# LM_HTR_001_TEST.net
KiCad netlist of a schematic drawn in Altium Designer
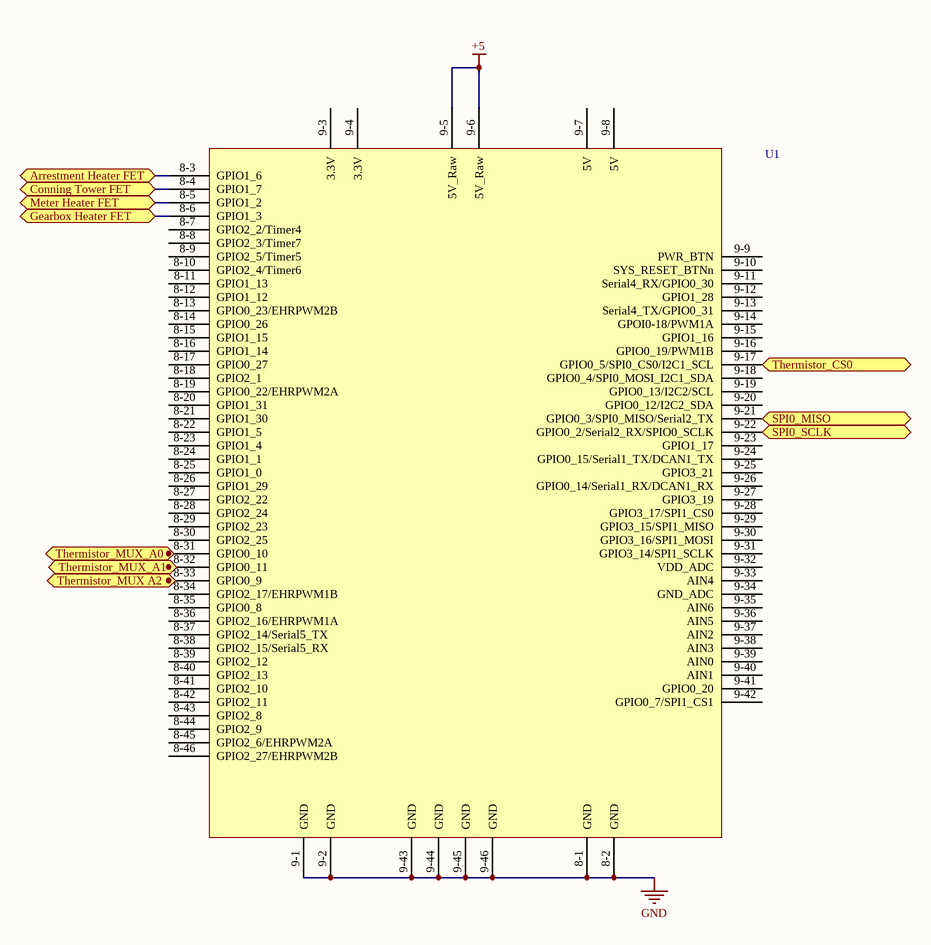
[diagram p0: LM_HTR_001_TEST.SchDoc]

(export (version "E")
  (design (tool "Eeschema 10.0.6"))
  (components
    (comp (ref "U1")
      (value "BBB")
      (footprint "Beaglebone Black")
      (description "Beaglebone Black")
      (libsource (lib "ZLS_Schematic_lib") (part "Beaglebone_Black"))
    )
  )
  (nets
    (net (code "1") (name "+5") (class "Default")
      (node (ref "U1") (pin "9-5") (pinfunction "5V_Raw_9-5") (pintype "passive"))
      (node (ref "U1") (pin "9-6") (pinfunction "5V_Raw_9-6") (pintype "passive"))
    )
    (net (code "2") (name "/Arrestment Heater FET") (class "Default")
      (node (ref "U1") (pin "8-3") (pinfunction "GPIO1_6_8-3") (pintype "passive"))
    )
    (net (code "3") (name "/Conning Tower FET") (class "Default")
      (node (ref "U1") (pin "8-4") (pinfunction "GPIO1_7_8-4") (pintype "passive"))
    )
    (net (code "4") (name "/Gearbox Heater FET") (class "Default")
      (node (ref "U1") (pin "8-6") (pinfunction "GPIO1_3_8-6") (pintype "passive"))
    )
    (net (code "5") (name "/Meter Heater FET") (class "Default")
      (node (ref "U1") (pin "8-5") (pinfunction "GPIO1_2_8-5") (pintype "passive"))
    )
    (net (code "6") (name "/SPI0_MISO") (class "Default")
      (node (ref "U1") (pin "9-21") (pinfunction "GPIO0_3/SPI0_MISO/Serial2_TX_9-21") (pintype "passive"))
    )
    (net (code "7") (name "/SPI0_SCLK") (class "Default")
      (node (ref "U1") (pin "9-22") (pinfunction "GPIO0_2/Serial2_RX/SPIO0_SCLK_9-22") (pintype "passive"))
    )
    (net (code "8") (name "/Thermistor_CS0") (class "Default")
      (node (ref "U1") (pin "9-17") (pinfunction "GPIO0_5/SPI0_CS0/I2C1_SCL_9-17") (pintype "passive"))
    )
    (net (code "12") (name "GND") (class "Default")
      (node (ref "U1") (pin "8-1") (pinfunction "GND_8-1") (pintype "passive"))
      (node (ref "U1") (pin "8-2") (pinfunction "GND_8-2") (pintype "passive"))
      (node (ref "U1") (pin "9-1") (pinfunction "GND_9-1") (pintype "passive"))
      (node (ref "U1") (pin "9-2") (pinfunction "GND_9-2") (pintype "passive"))
      (node (ref "U1") (pin "9-43") (pinfunction "GND_9-43") (pintype "passive"))
      (node (ref "U1") (pin "9-44") (pinfunction "GND_9-44") (pintype "passive"))
      (node (ref "U1") (pin "9-45") (pinfunction "GND_9-45") (pintype "passive"))
      (node (ref "U1") (pin "9-46") (pinfunction "GND_9-46") (pintype "passive"))
    )
    (net (code "13") (name "unconnected-(U1-3.3V-Pad9-3)") (class "Default")
      (node (ref "U1") (pin "9-3") (pinfunction "3.3V_9-3") (pintype "passive"))
    )
    (net (code "14") (name "unconnected-(U1-3.3V-Pad9-4)") (class "Default")
      (node (ref "U1") (pin "9-4") (pinfunction "3.3V_9-4") (pintype "passive"))
    )
    (net (code "15") (name "unconnected-(U1-5V-Pad9-7)") (class "Default")
      (node (ref "U1") (pin "9-7") (pinfunction "5V_9-7") (pintype "passive"))
    )
    (net (code "16") (name "unconnected-(U1-5V-Pad9-8)") (class "Default")
      (node (ref "U1") (pin "9-8") (pinfunction "5V_9-8") (pintype "passive"))
    )
    (net (code "17") (name "unconnected-(U1-AIN0-Pad9-39)") (class "Default")
      (node (ref "U1") (pin "9-39") (pinfunction "AIN0_9-39") (pintype "passive"))
    )
    (net (code "18") (name "unconnected-(U1-AIN1-Pad9-40)") (class "Default")
      (node (ref "U1") (pin "9-40") (pinfunction "AIN1_9-40") (pintype "passive"))
    )
    (net (code "19") (name "unconnected-(U1-AIN2-Pad9-37)") (class "Default")
      (node (ref "U1") (pin "9-37") (pinfunction "AIN2_9-37") (pintype "passive"))
    )
    (net (code "20") (name "unconnected-(U1-AIN3-Pad9-38)") (class "Default")
      (node (ref "U1") (pin "9-38") (pinfunction "AIN3_9-38") (pintype "passive"))
    )
    (net (code "21") (name "unconnected-(U1-AIN4-Pad9-33)") (class "Default")
      (node (ref "U1") (pin "9-33") (pinfunction "AIN4_9-33") (pintype "passive"))
    )
    (net (code "22") (name "unconnected-(U1-AIN5-Pad9-36)") (class "Default")
      (node (ref "U1") (pin "9-36") (pinfunction "AIN5_9-36") (pintype "passive"))
    )
    (net (code "23") (name "unconnected-(U1-AIN6-Pad9-35)") (class "Default")
      (node (ref "U1") (pin "9-35") (pinfunction "AIN6_9-35") (pintype "passive"))
    )
    (net (code "24") (name "unconnected-(U1-GND_ADC-Pad9-34)") (class "Default")
      (node (ref "U1") (pin "9-34") (pinfunction "GND_ADC_9-34") (pintype "passive"))
    )
    (net (code "25") (name "unconnected-(U1-GPIO0_4{slash}SPI0_MOSI_I2C1_SDA-Pad9-18)") (class "Default")
      (node (ref "U1") (pin "9-18") (pinfunction "GPIO0_4/SPI0_MOSI_I2C1_SDA_9-18") (pintype "passive"))
    )
    (net (code "26") (name "unconnected-(U1-GPIO0_7{slash}SPI1_CS1-Pad9-42)") (class "Default")
      (node (ref "U1") (pin "9-42") (pinfunction "GPIO0_7/SPI1_CS1_9-42") (pintype "passive"))
    )
    (net (code "27") (name "unconnected-(U1-GPIO0_8-Pad8-35)") (class "Default")
      (node (ref "U1") (pin "8-35") (pinfunction "GPIO0_8_8-35") (pintype "passive"))
    )
    (net (code "28") (name "unconnected-(U1-GPIO0_9-Pad8-33)") (class "Default")
      (node (ref "U1") (pin "8-33") (pinfunction "GPIO0_9_8-33") (pintype "passive"))
    )
    (net (code "29") (name "unconnected-(U1-GPIO0_10-Pad8-31)") (class "Default")
      (node (ref "U1") (pin "8-31") (pinfunction "GPIO0_10_8-31") (pintype "passive"))
    )
    (net (code "30") (name "unconnected-(U1-GPIO0_11-Pad8-32)") (class "Default")
      (node (ref "U1") (pin "8-32") (pinfunction "GPIO0_11_8-32") (pintype "passive"))
    )
    (net (code "31") (name "unconnected-(U1-GPIO0_12{slash}I2C2_SDA-Pad9-20)") (class "Default")
      (node (ref "U1") (pin "9-20") (pinfunction "GPIO0_12/I2C2_SDA_9-20") (pintype "passive"))
    )
    (net (code "32") (name "unconnected-(U1-GPIO0_13{slash}I2C2{slash}SCL-Pad9-19)") (class "Default")
      (node (ref "U1") (pin "9-19") (pinfunction "GPIO0_13/I2C2/SCL_9-19") (pintype "passive"))
    )
    (net (code "33") (name "unconnected-(U1-GPIO0_14{slash}Serial1_RX{slash}DCAN1_RX-Pad9-26)") (class "Default")
      (node (ref "U1") (pin "9-26") (pinfunction "GPIO0_14/Serial1_RX/DCAN1_RX_9-26") (pintype "passive"))
    )
    (net (code "34") (name "unconnected-(U1-GPIO0_15{slash}Serial1_TX{slash}DCAN1_TX-Pad9-24)") (class "Default")
      (node (ref "U1") (pin "9-24") (pinfunction "GPIO0_15/Serial1_TX/DCAN1_TX_9-24") (pintype "passive"))
    )
    (net (code "35") (name "unconnected-(U1-GPIO0_19{slash}PWM1B-Pad9-16)") (class "Default")
      (node (ref "U1") (pin "9-16") (pinfunction "GPIO0_19/PWM1B_9-16") (pintype "passive"))
    )
    (net (code "36") (name "unconnected-(U1-GPIO0_20-Pad9-41)") (class "Default")
      (node (ref "U1") (pin "9-41") (pinfunction "GPIO0_20_9-41") (pintype "passive"))
    )
    (net (code "37") (name "unconnected-(U1-GPIO0_22{slash}EHRPWM2A-Pad8-19)") (class "Default")
      (node (ref "U1") (pin "8-19") (pinfunction "GPIO0_22/EHRPWM2A_8-19") (pintype "passive"))
    )
    (net (code "38") (name "unconnected-(U1-GPIO0_23{slash}EHRPWM2B-Pad8-13)") (class "Default")
      (node (ref "U1") (pin "8-13") (pinfunction "GPIO0_23/EHRPWM2B_8-13") (pintype "passive"))
    )
    (net (code "39") (name "unconnected-(U1-GPIO0_26-Pad8-14)") (class "Default")
      (node (ref "U1") (pin "8-14") (pinfunction "GPIO0_26_8-14") (pintype "passive"))
    )
    (net (code "40") (name "unconnected-(U1-GPIO0_27-Pad8-17)") (class "Default")
      (node (ref "U1") (pin "8-17") (pinfunction "GPIO0_27_8-17") (pintype "passive"))
    )
    (net (code "41") (name "unconnected-(U1-GPIO1_0-Pad8-25)") (class "Default")
      (node (ref "U1") (pin "8-25") (pinfunction "GPIO1_0_8-25") (pintype "passive"))
    )
    (net (code "42") (name "unconnected-(U1-GPIO1_1-Pad8-24)") (class "Default")
      (node (ref "U1") (pin "8-24") (pinfunction "GPIO1_1_8-24") (pintype "passive"))
    )
    (net (code "43") (name "unconnected-(U1-GPIO1_4-Pad8-23)") (class "Default")
      (node (ref "U1") (pin "8-23") (pinfunction "GPIO1_4_8-23") (pintype "passive"))
    )
    (net (code "44") (name "unconnected-(U1-GPIO1_5-Pad8-22)") (class "Default")
      (node (ref "U1") (pin "8-22") (pinfunction "GPIO1_5_8-22") (pintype "passive"))
    )
    (net (code "45") (name "unconnected-(U1-GPIO1_12-Pad8-12)") (class "Default")
      (node (ref "U1") (pin "8-12") (pinfunction "GPIO1_12_8-12") (pintype "passive"))
    )
    (net (code "46") (name "unconnected-(U1-GPIO1_13-Pad8-11)") (class "Default")
      (node (ref "U1") (pin "8-11") (pinfunction "GPIO1_13_8-11") (pintype "passive"))
    )
    (net (code "47") (name "unconnected-(U1-GPIO1_14-Pad8-16)") (class "Default")
      (node (ref "U1") (pin "8-16") (pinfunction "GPIO1_14_8-16") (pintype "passive"))
    )
    (net (code "48") (name "unconnected-(U1-GPIO1_15-Pad8-15)") (class "Default")
      (node (ref "U1") (pin "8-15") (pinfunction "GPIO1_15_8-15") (pintype "passive"))
    )
    (net (code "49") (name "unconnected-(U1-GPIO1_16-Pad9-15)") (class "Default")
      (node (ref "U1") (pin "9-15") (pinfunction "GPIO1_16_9-15") (pintype "passive"))
    )
    (net (code "50") (name "unconnected-(U1-GPIO1_17-Pad9-23)") (class "Default")
      (node (ref "U1") (pin "9-23") (pinfunction "GPIO1_17_9-23") (pintype "passive"))
    )
    (net (code "51") (name "unconnected-(U1-GPIO1_28-Pad9-12)") (class "Default")
      (node (ref "U1") (pin "9-12") (pinfunction "GPIO1_28_9-12") (pintype "passive"))
    )
    (net (code "52") (name "unconnected-(U1-GPIO1_29-Pad8-26)") (class "Default")
      (node (ref "U1") (pin "8-26") (pinfunction "GPIO1_29_8-26") (pintype "passive"))
    )
    (net (code "53") (name "unconnected-(U1-GPIO1_30-Pad8-21)") (class "Default")
      (node (ref "U1") (pin "8-21") (pinfunction "GPIO1_30_8-21") (pintype "passive"))
    )
    (net (code "54") (name "unconnected-(U1-GPIO1_31-Pad8-20)") (class "Default")
      (node (ref "U1") (pin "8-20") (pinfunction "GPIO1_31_8-20") (pintype "passive"))
    )
    (net (code "55") (name "unconnected-(U1-GPIO2_1-Pad8-18)") (class "Default")
      (node (ref "U1") (pin "8-18") (pinfunction "GPIO2_1_8-18") (pintype "passive"))
    )
    (net (code "56") (name "unconnected-(U1-GPIO2_2{slash}Timer4-Pad8-7)") (class "Default")
      (node (ref "U1") (pin "8-7") (pinfunction "GPIO2_2/Timer4_8-7") (pintype "passive"))
    )
    (net (code "57") (name "unconnected-(U1-GPIO2_3{slash}Timer7-Pad8-8)") (class "Default")
      (node (ref "U1") (pin "8-8") (pinfunction "GPIO2_3/Timer7_8-8") (pintype "passive"))
    )
    (net (code "58") (name "unconnected-(U1-GPIO2_4{slash}Timer6-Pad8-10)") (class "Default")
      (node (ref "U1") (pin "8-10") (pinfunction "GPIO2_4/Timer6_8-10") (pintype "passive"))
    )
    (net (code "59") (name "unconnected-(U1-GPIO2_5{slash}Timer5-Pad8-9)") (class "Default")
      (node (ref "U1") (pin "8-9") (pinfunction "GPIO2_5/Timer5_8-9") (pintype "passive"))
    )
    (net (code "60") (name "unconnected-(U1-GPIO2_6{slash}EHRPWM2A-Pad8-45)") (class "Default")
      (node (ref "U1") (pin "8-45") (pinfunction "GPIO2_6/EHRPWM2A_8-45") (pintype "passive"))
    )
    (net (code "61") (name "unconnected-(U1-GPIO2_8-Pad8-43)") (class "Default")
      (node (ref "U1") (pin "8-43") (pinfunction "GPIO2_8_8-43") (pintype "passive"))
    )
    (net (code "62") (name "unconnected-(U1-GPIO2_9-Pad8-44)") (class "Default")
      (node (ref "U1") (pin "8-44") (pinfunction "GPIO2_9_8-44") (pintype "passive"))
    )
    (net (code "63") (name "unconnected-(U1-GPIO2_10-Pad8-41)") (class "Default")
      (node (ref "U1") (pin "8-41") (pinfunction "GPIO2_10_8-41") (pintype "passive"))
    )
    (net (code "64") (name "unconnected-(U1-GPIO2_11-Pad8-42)") (class "Default")
      (node (ref "U1") (pin "8-42") (pinfunction "GPIO2_11_8-42") (pintype "passive"))
    )
    (net (code "65") (name "unconnected-(U1-GPIO2_12-Pad8-39)") (class "Default")
      (node (ref "U1") (pin "8-39") (pinfunction "GPIO2_12_8-39") (pintype "passive"))
    )
    (net (code "66") (name "unconnected-(U1-GPIO2_13-Pad8-40)") (class "Default")
      (node (ref "U1") (pin "8-40") (pinfunction "GPIO2_13_8-40") (pintype "passive"))
    )
    (net (code "67") (name "unconnected-(U1-GPIO2_14{slash}Serial5_TX-Pad8-37)") (class "Default")
      (node (ref "U1") (pin "8-37") (pinfunction "GPIO2_14/Serial5_TX_8-37") (pintype "passive"))
    )
    (net (code "68") (name "unconnected-(U1-GPIO2_15{slash}Serial5_RX-Pad8-38)") (class "Default")
      (node (ref "U1") (pin "8-38") (pinfunction "GPIO2_15/Serial5_RX_8-38") (pintype "passive"))
    )
    (net (code "69") (name "unconnected-(U1-GPIO2_16{slash}EHRPWM1A-Pad8-36)") (class "Default")
      (node (ref "U1") (pin "8-36") (pinfunction "GPIO2_16/EHRPWM1A_8-36") (pintype "passive"))
    )
    (net (code "70") (name "unconnected-(U1-GPIO2_17{slash}EHRPWM1B-Pad8-34)") (class "Default")
      (node (ref "U1") (pin "8-34") (pinfunction "GPIO2_17/EHRPWM1B_8-34") (pintype "passive"))
    )
    (net (code "71") (name "unconnected-(U1-GPIO2_22-Pad8-27)") (class "Default")
      (node (ref "U1") (pin "8-27") (pinfunction "GPIO2_22_8-27") (pintype "passive"))
    )
    (net (code "72") (name "unconnected-(U1-GPIO2_23-Pad8-29)") (class "Default")
      (node (ref "U1") (pin "8-29") (pinfunction "GPIO2_23_8-29") (pintype "passive"))
    )
    (net (code "73") (name "unconnected-(U1-GPIO2_24-Pad8-28)") (class "Default")
      (node (ref "U1") (pin "8-28") (pinfunction "GPIO2_24_8-28") (pintype "passive"))
    )
    (net (code "74") (name "unconnected-(U1-GPIO2_25-Pad8-30)") (class "Default")
      (node (ref "U1") (pin "8-30") (pinfunction "GPIO2_25_8-30") (pintype "passive"))
    )
    (net (code "75") (name "unconnected-(U1-GPIO2_27{slash}EHRPWM2B-Pad8-46)") (class "Default")
      (node (ref "U1") (pin "8-46") (pinfunction "GPIO2_27/EHRPWM2B_8-46") (pintype "passive"))
    )
    (net (code "76") (name "unconnected-(U1-GPIO3_14{slash}SPI1_SCLK-Pad9-31)") (class "Default")
      (node (ref "U1") (pin "9-31") (pinfunction "GPIO3_14/SPI1_SCLK_9-31") (pintype "passive"))
    )
    (net (code "77") (name "unconnected-(U1-GPIO3_15{slash}SPI1_MISO-Pad9-29)") (class "Default")
      (node (ref "U1") (pin "9-29") (pinfunction "GPIO3_15/SPI1_MISO_9-29") (pintype "passive"))
    )
    (net (code "78") (name "unconnected-(U1-GPIO3_16{slash}SPI1_MOSI-Pad9-30)") (class "Default")
      (node (ref "U1") (pin "9-30") (pinfunction "GPIO3_16/SPI1_MOSI_9-30") (pintype "passive"))
    )
    (net (code "79") (name "unconnected-(U1-GPIO3_17{slash}SPI1_CS0-Pad9-28)") (class "Default")
      (node (ref "U1") (pin "9-28") (pinfunction "GPIO3_17/SPI1_CS0_9-28") (pintype "passive"))
    )
    (net (code "80") (name "unconnected-(U1-GPIO3_19-Pad9-27)") (class "Default")
      (node (ref "U1") (pin "9-27") (pinfunction "GPIO3_19_9-27") (pintype "passive"))
    )
    (net (code "81") (name "unconnected-(U1-GPIO3_21-Pad9-25)") (class "Default")
      (node (ref "U1") (pin "9-25") (pinfunction "GPIO3_21_9-25") (pintype "passive"))
    )
    (net (code "82") (name "unconnected-(U1-GPOI0-18{slash}PWM1A-Pad9-14)") (class "Default")
      (node (ref "U1") (pin "9-14") (pinfunction "GPOI0-18/PWM1A_9-14") (pintype "passive"))
    )
    (net (code "83") (name "unconnected-(U1-PWR_BTN-Pad9-9)") (class "Default")
      (node (ref "U1") (pin "9-9") (pinfunction "PWR_BTN_9-9") (pintype "passive"))
    )
    (net (code "84") (name "unconnected-(U1-SYS_RESET_BTNn-Pad9-10)") (class "Default")
      (node (ref "U1") (pin "9-10") (pinfunction "SYS_RESET_BTNn_9-10") (pintype "passive"))
    )
    (net (code "85") (name "unconnected-(U1-Serial4_RX{slash}GPIO0_30-Pad9-11)") (class "Default")
      (node (ref "U1") (pin "9-11") (pinfunction "Serial4_RX/GPIO0_30_9-11") (pintype "passive"))
    )
    (net (code "86") (name "unconnected-(U1-Serial4_TX{slash}GPIO0_31-Pad9-13)") (class "Default")
      (node (ref "U1") (pin "9-13") (pinfunction "Serial4_TX/GPIO0_31_9-13") (pintype "passive"))
    )
    (net (code "87") (name "unconnected-(U1-VDD_ADC-Pad9-32)") (class "Default")
      (node (ref "U1") (pin "9-32") (pinfunction "VDD_ADC_9-32") (pintype "passive"))
    )
  )
)
